# th-lora.net
KiCad netlist of a schematic drawn in EAGLE
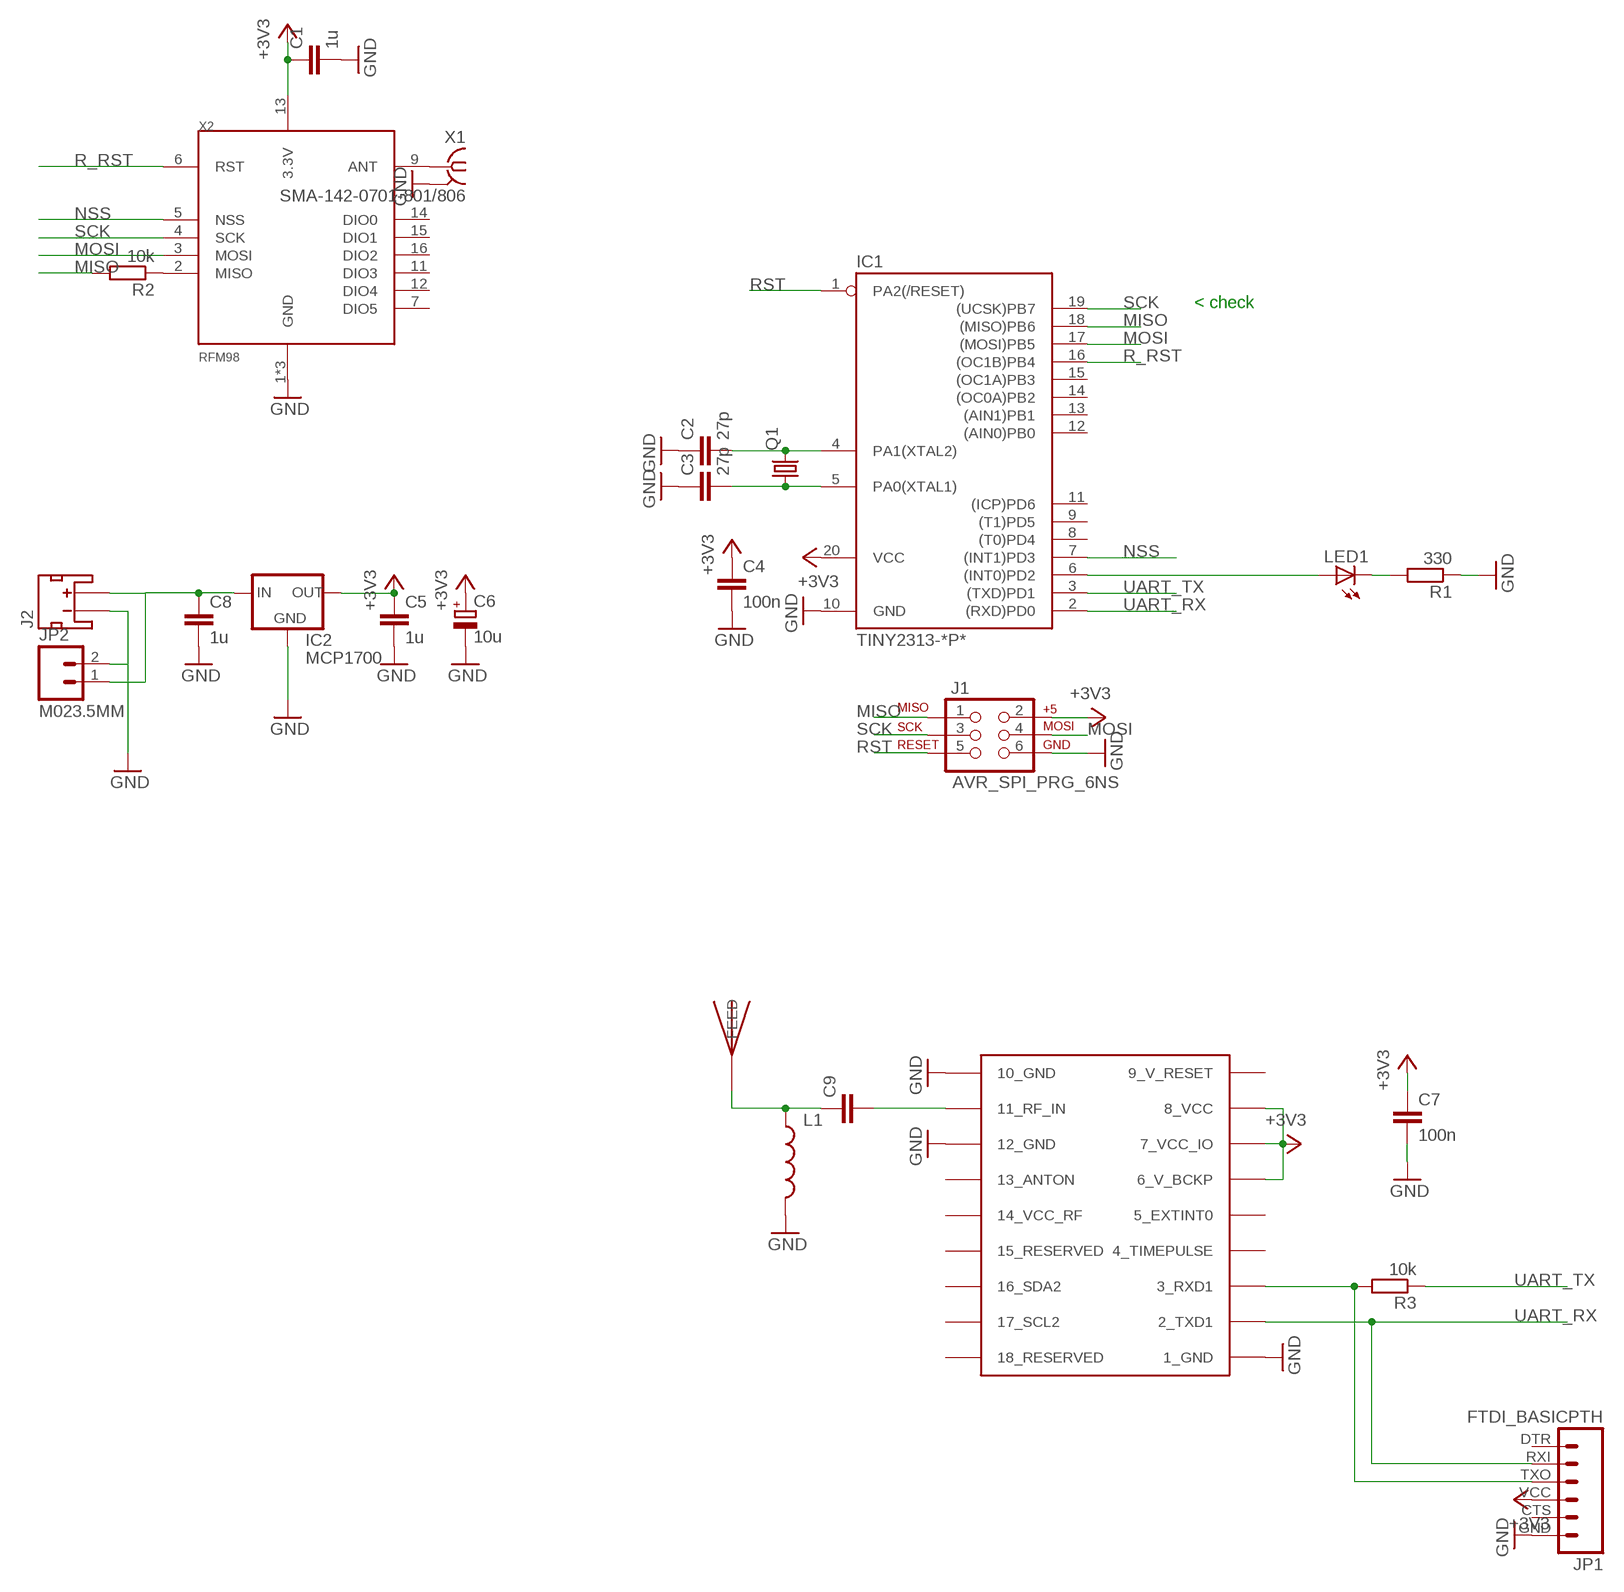
[diagram p0: schematic, sheet 1]

(export (version "E")
  (design (tool "Eeschema 10.0.6"))
  (components
    (comp (ref "C1")
      (value "1u")
      (footprint "eagle-import:C050-025X075")
      (libsource (lib "eagle-import") (part "C-EU050-025X075"))
    )
    (comp (ref "C2")
      (value "27p")
      (footprint "eagle-import:C050-025X075")
      (libsource (lib "eagle-import") (part "C-EU050-025X075"))
    )
    (comp (ref "C3")
      (value "27p")
      (footprint "eagle-import:C050-025X075")
      (libsource (lib "eagle-import") (part "C-EU050-025X075"))
    )
    (comp (ref "C4")
      (value "100n")
      (footprint "eagle-import:C050-025X075")
      (libsource (lib "eagle-import") (part "C-EU050-025X075"))
    )
    (comp (ref "C5")
      (value "1u")
      (footprint "eagle-import:C050-025X075")
      (libsource (lib "eagle-import") (part "C-EU050-025X075"))
    )
    (comp (ref "C6")
      (value "10u")
      (footprint "eagle-import:E2,5-5")
      (libsource (lib "eagle-import") (part "CPOL-EUE2.5-5"))
    )
    (comp (ref "C7")
      (value "100n")
      (footprint "eagle-import:C050-025X075")
      (libsource (lib "eagle-import") (part "C-EU050-025X075"))
    )
    (comp (ref "C8")
      (value "1u")
      (footprint "eagle-import:C050-025X075")
      (libsource (lib "eagle-import") (part "C-EU050-025X075"))
    )
    (comp (ref "C9")
      (value "C-EUC0603")
      (footprint "eagle-import:C0603")
      (libsource (lib "eagle-import") (part "C-EUC0603"))
    )
    (comp (ref "IC1")
      (value "TINY2313-*P*")
      (footprint "eagle-import:DIL20")
      (libsource (lib "eagle-import") (part "TINY2313-P"))
    )
    (comp (ref "IC2")
      (value "MCP1700")
      (footprint "eagle-import:TO92-INLINE")
      (libsource (lib "eagle-import") (part "MCP1700"))
    )
    (comp (ref "J1")
      (value "AVR_SPI_PRG_6NS")
      (footprint "eagle-import:2X3-NS")
      (libsource (lib "eagle-import") (part "AVR_SPI_PRG_6NS"))
    )
    (comp (ref "J2")
      (value "JST_2MM_MALE")
      (footprint "eagle-import:JST-2-SMD")
      (libsource (lib "eagle-import") (part "JST_2MM_MALE"))
    )
    (comp (ref "JP1")
      (value "FTDI_BASICPTH")
      (footprint "eagle-import:FTDI_BASIC")
      (libsource (lib "eagle-import") (part "FTDI_BASICPTH"))
    )
    (comp (ref "JP2")
      (value "M023.5MM")
      (footprint "eagle-import:SCREWTERMINAL-3.5MM-2")
      (libsource (lib "eagle-import") (part "M023.5MM"))
    )
    (comp (ref "L1")
      (value "INDUCTOR0603")
      (footprint "eagle-import:0603")
      (libsource (lib "eagle-import") (part "INDUCTOR0603"))
    )
    (comp (ref "LED1")
      (value "LED3MM")
      (footprint "eagle-import:LED3MM")
      (libsource (lib "eagle-import") (part "LED3MM"))
    )
    (comp (ref "Q1")
      (value "CRYSTALHC49S")
      (footprint "eagle-import:HC49_S")
      (libsource (lib "eagle-import") (part "CRYSTALHC49S"))
    )
    (comp (ref "R1")
      (value "330")
      (footprint "eagle-import:0204_7")
      (libsource (lib "eagle-import") (part "R-EU_0204/7"))
    )
    (comp (ref "R2")
      (value "10k")
      (footprint "eagle-import:0204_7")
      (libsource (lib "eagle-import") (part "R-EU_0204/7"))
    )
    (comp (ref "R3")
      (value "10k")
      (footprint "eagle-import:0204_7")
      (libsource (lib "eagle-import") (part "R-EU_0204/7"))
    )
    (comp (ref "U$3")
      (value "JTI_ANTENNA-1575AT43A40")
      (footprint "eagle-import:JTI_ANTENNA-1575AT43A40")
      (libsource (lib "eagle-import") (part "JTI_ANTENNA-1575AT43A40"))
    )
    (comp (ref "X1")
      (value "SMA-142-0701-801/806")
      (footprint "eagle-import:J502-ND-142-0701-801_806")
      (fields (field (name "MF") "JOHNSON COMPONENTS") (field (name "MPN") "142-0701-801"))
      (libsource (lib "eagle-import") (part "SMA-142-0701-801/806"))
    )
    (comp (ref "X2")
      (value "RFM98")
      (footprint "eagle-import:RFM97")
      (libsource (lib "eagle-import") (part "RFM98"))
    )
    (comp (ref "X3")
      (value "UBLOX_MAX")
      (footprint "eagle-import:UBLOX_MAX")
      (libsource (lib "eagle-import") (part "UBLOX_MAX"))
    )
  )
  (nets
    (net (code "1") (name "+3V3") (class "Default")
      (node (ref "C1") (pin "1") (pinfunction "1_1") (pintype "passive"))
      (node (ref "C4") (pin "1") (pinfunction "1_1") (pintype "passive"))
      (node (ref "C5") (pin "1") (pinfunction "1_1") (pintype "passive"))
      (node (ref "C6") (pin "+") (pinfunction "+_+") (pintype "passive"))
      (node (ref "C7") (pin "1") (pinfunction "1_1") (pintype "passive"))
      (node (ref "IC1") (pin "20") (pinfunction "VCC_20") (pintype "power_in"))
      (node (ref "IC2") (pin "VOUT") (pinfunction "OUT_VOUT") (pintype "passive"))
      (node (ref "J1") (pin "2") (pinfunction "2_2") (pintype "passive"))
      (node (ref "JP1") (pin "VCC") (pinfunction "4_VCC") (pintype "passive"))
      (node (ref "X2") (pin "13") (pinfunction "3.3V_13") (pintype "power_in"))
      (node (ref "X3") (pin "6_V_BCKP") (pinfunction "6_V_BCKP_6_V_BCKP") (pintype "bidirectional"))
      (node (ref "X3") (pin "7_VCC_IO") (pinfunction "7_VCC_IO_7_VCC_IO") (pintype "power_in"))
      (node (ref "X3") (pin "8_VCC") (pinfunction "8_VCC_8_VCC") (pintype "power_in"))
    )
    (net (code "2") (name "/9_V_RESET") (class "Default")
      (node (ref "X3") (pin "9_V_RESET") (pinfunction "9_V_RESET_9_V_RESET") (pintype "power_in"))
    )
    (net (code "3") (name "/MISO") (class "Default")
      (node (ref "IC1") (pin "18") (pinfunction "(MISO)PB6_18") (pintype "bidirectional"))
      (node (ref "J1") (pin "1") (pinfunction "1_1") (pintype "passive"))
      (node (ref "R2") (pin "2") (pinfunction "2_2") (pintype "passive"))
    )
    (net (code "4") (name "/MOSI") (class "Default")
      (node (ref "IC1") (pin "17") (pinfunction "(MOSI)PB5_17") (pintype "bidirectional"))
      (node (ref "J1") (pin "4") (pinfunction "4_4") (pintype "passive"))
      (node (ref "X2") (pin "3") (pinfunction "MOSI_3") (pintype "input"))
    )
    (net (code "5") (name "/NSS") (class "Default")
      (node (ref "IC1") (pin "7") (pinfunction "(INT1)PD3_7") (pintype "bidirectional"))
      (node (ref "X2") (pin "5") (pinfunction "NSS_5") (pintype "input"))
    )
    (net (code "6") (name "/RST") (class "Default")
      (node (ref "IC1") (pin "1") (pinfunction "PA2(/RESET)_1") (pintype "input"))
      (node (ref "J1") (pin "5") (pinfunction "5_5") (pintype "passive"))
    )
    (net (code "7") (name "/R_RST") (class "Default")
      (node (ref "IC1") (pin "16") (pinfunction "(OC1B)PB4_16") (pintype "bidirectional"))
      (node (ref "X2") (pin "6") (pinfunction "RST_6") (pintype "input"))
    )
    (net (code "8") (name "/SCK") (class "Default")
      (node (ref "IC1") (pin "19") (pinfunction "(UCSK)PB7_19") (pintype "bidirectional"))
      (node (ref "J1") (pin "3") (pinfunction "3_3") (pintype "passive"))
      (node (ref "X2") (pin "4") (pinfunction "SCK_4") (pintype "input"))
    )
    (net (code "9") (name "/UART_RX") (class "Default")
      (node (ref "IC1") (pin "2") (pinfunction "(RXD)PD0_2") (pintype "bidirectional"))
      (node (ref "JP1") (pin "RXI") (pinfunction "2_RXI") (pintype "passive"))
      (node (ref "X3") (pin "2_TXD1") (pinfunction "2_TXD1_2_TXD1") (pintype "bidirectional"))
    )
    (net (code "10") (name "/UART_TX") (class "Default")
      (node (ref "IC1") (pin "3") (pinfunction "(TXD)PD1_3") (pintype "bidirectional"))
      (node (ref "R3") (pin "1") (pinfunction "1_1") (pintype "passive"))
    )
    (net (code "11") (name "GND") (class "Default")
      (node (ref "C1") (pin "2") (pinfunction "2_2") (pintype "passive"))
      (node (ref "C2") (pin "1") (pinfunction "1_1") (pintype "passive"))
      (node (ref "C3") (pin "1") (pinfunction "1_1") (pintype "passive"))
      (node (ref "C4") (pin "2") (pinfunction "2_2") (pintype "passive"))
      (node (ref "C5") (pin "2") (pinfunction "2_2") (pintype "passive"))
      (node (ref "C6") (pin "-") (pinfunction "-_-") (pintype "passive"))
      (node (ref "C7") (pin "2") (pinfunction "2_2") (pintype "passive"))
      (node (ref "C8") (pin "2") (pinfunction "2_2") (pintype "passive"))
      (node (ref "IC1") (pin "10") (pinfunction "GND_10") (pintype "power_in"))
      (node (ref "IC2") (pin "GND") (pinfunction "GND_GND") (pintype "input"))
      (node (ref "J1") (pin "6") (pinfunction "6_6") (pintype "passive"))
      (node (ref "J2") (pin "1") (pinfunction "-_1") (pintype "bidirectional"))
      (node (ref "JP1") (pin "GND") (pinfunction "6_GND") (pintype "passive"))
      (node (ref "JP2") (pin "2") (pinfunction "2_2") (pintype "passive"))
      (node (ref "L1") (pin "2") (pinfunction "2_2") (pintype "passive"))
      (node (ref "R1") (pin "1") (pinfunction "1_1") (pintype "passive"))
      (node (ref "X1") (pin "G@1") (pinfunction "2_G@1") (pintype "passive"))
      (node (ref "X1") (pin "G@2") (pinfunction "2_G@2") (pintype "passive"))
      (node (ref "X1") (pin "G@3") (pinfunction "2_G@3") (pintype "passive"))
      (node (ref "X1") (pin "G@4") (pinfunction "2_G@4") (pintype "passive"))
      (node (ref "X2") (pin "1") (pinfunction "GND_1") (pintype "power_in"))
      (node (ref "X2") (pin "10") (pinfunction "GND_10") (pintype "power_in"))
      (node (ref "X2") (pin "8") (pinfunction "GND_8") (pintype "power_in"))
      (node (ref "X3") (pin "10_GND") (pinfunction "10_GND_10_GND") (pintype "power_in"))
      (node (ref "X3") (pin "12_GND") (pinfunction "12_GND_12_GND") (pintype "power_in"))
      (node (ref "X3") (pin "1_GND") (pinfunction "1_GND_1_GND") (pintype "power_in"))
    )
    (net (code "12") (name "Net-(C9-Pad1)") (class "Default")
      (node (ref "C9") (pin "1") (pinfunction "1_1") (pintype "passive"))
      (node (ref "L1") (pin "1") (pinfunction "1_1") (pintype "passive"))
      (node (ref "U$3") (pin "FEED") (pinfunction "FEED_FEED") (pintype "bidirectional"))
    )
    (net (code "13") (name "Net-(C9-Pad2)") (class "Default")
      (node (ref "C9") (pin "2") (pinfunction "2_2") (pintype "passive"))
      (node (ref "X3") (pin "11_RF_IN") (pinfunction "11_RF_IN_11_RF_IN") (pintype "bidirectional"))
    )
    (net (code "14") (name "Net-(IC1-(INT0)PD2)") (class "Default")
      (node (ref "IC1") (pin "6") (pinfunction "(INT0)PD2_6") (pintype "bidirectional"))
      (node (ref "LED1") (pin "A") (pinfunction "A_A") (pintype "passive"))
    )
    (net (code "15") (name "Net-(IC1-PA0(XTAL1))") (class "Default")
      (node (ref "C3") (pin "2") (pinfunction "2_2") (pintype "passive"))
      (node (ref "IC1") (pin "5") (pinfunction "PA0(XTAL1)_5") (pintype "bidirectional"))
      (node (ref "Q1") (pin "1") (pinfunction "1_1") (pintype "passive"))
    )
    (net (code "16") (name "Net-(IC1-PA1(XTAL2))") (class "Default")
      (node (ref "C2") (pin "2") (pinfunction "2_2") (pintype "passive"))
      (node (ref "IC1") (pin "4") (pinfunction "PA1(XTAL2)_4") (pintype "bidirectional"))
      (node (ref "Q1") (pin "2") (pinfunction "2_2") (pintype "passive"))
    )
    (net (code "17") (name "Net-(IC2-IN)") (class "Default")
      (node (ref "C8") (pin "1") (pinfunction "1_1") (pintype "passive"))
      (node (ref "IC2") (pin "VIN") (pinfunction "IN_VIN") (pintype "input"))
      (node (ref "J2") (pin "2") (pinfunction "+_2") (pintype "bidirectional"))
      (node (ref "JP2") (pin "1") (pinfunction "1_1") (pintype "passive"))
    )
    (net (code "18") (name "Net-(JP1-3)") (class "Default")
      (node (ref "JP1") (pin "TXO") (pinfunction "3_TXO") (pintype "passive"))
      (node (ref "R3") (pin "2") (pinfunction "2_2") (pintype "passive"))
      (node (ref "X3") (pin "3_RXD1") (pinfunction "3_RXD1_3_RXD1") (pintype "bidirectional"))
    )
    (net (code "19") (name "Net-(LED1-C)") (class "Default")
      (node (ref "LED1") (pin "K") (pinfunction "C_K") (pintype "passive"))
      (node (ref "R1") (pin "2") (pinfunction "2_2") (pintype "passive"))
    )
    (net (code "20") (name "Net-(X2-ANT)") (class "Default")
      (node (ref "X1") (pin "1") (pinfunction "1_1") (pintype "passive"))
      (node (ref "X2") (pin "9") (pinfunction "ANT_9") (pintype "bidirectional"))
    )
    (net (code "21") (name "Net-(X2-MISO)") (class "Default")
      (node (ref "R2") (pin "1") (pinfunction "1_1") (pintype "passive"))
      (node (ref "X2") (pin "2") (pinfunction "MISO_2") (pintype "output"))
    )
    (net (code "22") (name "unconnected-(IC1-(AIN0)PB0-Pad12)") (class "Default")
      (node (ref "IC1") (pin "12") (pinfunction "(AIN0)PB0_12") (pintype "bidirectional"))
    )
    (net (code "23") (name "unconnected-(IC1-(AIN1)PB1-Pad13)") (class "Default")
      (node (ref "IC1") (pin "13") (pinfunction "(AIN1)PB1_13") (pintype "bidirectional"))
    )
    (net (code "24") (name "unconnected-(IC1-(ICP)PD6-Pad11)") (class "Default")
      (node (ref "IC1") (pin "11") (pinfunction "(ICP)PD6_11") (pintype "bidirectional"))
    )
    (net (code "25") (name "unconnected-(IC1-(OC0A)PB2-Pad14)") (class "Default")
      (node (ref "IC1") (pin "14") (pinfunction "(OC0A)PB2_14") (pintype "bidirectional"))
    )
    (net (code "26") (name "unconnected-(IC1-(OC1A)PB3-Pad15)") (class "Default")
      (node (ref "IC1") (pin "15") (pinfunction "(OC1A)PB3_15") (pintype "bidirectional"))
    )
    (net (code "27") (name "unconnected-(IC1-(T0)PD4-Pad8)") (class "Default")
      (node (ref "IC1") (pin "8") (pinfunction "(T0)PD4_8") (pintype "bidirectional"))
    )
    (net (code "28") (name "unconnected-(IC1-(T1)PD5-Pad9)") (class "Default")
      (node (ref "IC1") (pin "9") (pinfunction "(T1)PD5_9") (pintype "bidirectional"))
    )
    (net (code "29") (name "unconnected-(J2-PAD1-PadNC1)") (class "Default")
      (node (ref "J2") (pin "NC1") (pinfunction "PAD1_NC1") (pintype "bidirectional"))
    )
    (net (code "30") (name "unconnected-(J2-PAD2-PadNC2)") (class "Default")
      (node (ref "J2") (pin "NC2") (pinfunction "PAD2_NC2") (pintype "bidirectional"))
    )
    (net (code "31") (name "unconnected-(JP1-1-PadDTR)") (class "Default")
      (node (ref "JP1") (pin "DTR") (pinfunction "1_DTR") (pintype "passive"))
    )
    (net (code "32") (name "unconnected-(JP1-5-PadCTS)") (class "Default")
      (node (ref "JP1") (pin "CTS") (pinfunction "5_CTS") (pintype "passive"))
    )
    (net (code "33") (name "unconnected-(X2-DIO0-Pad14)") (class "Default")
      (node (ref "X2") (pin "14") (pinfunction "DIO0_14") (pintype "bidirectional"))
    )
    (net (code "34") (name "unconnected-(X2-DIO1-Pad15)") (class "Default")
      (node (ref "X2") (pin "15") (pinfunction "DIO1_15") (pintype "bidirectional"))
    )
    (net (code "35") (name "unconnected-(X2-DIO2-Pad16)") (class "Default")
      (node (ref "X2") (pin "16") (pinfunction "DIO2_16") (pintype "bidirectional"))
    )
    (net (code "36") (name "unconnected-(X2-DIO3-Pad11)") (class "Default")
      (node (ref "X2") (pin "11") (pinfunction "DIO3_11") (pintype "bidirectional"))
    )
    (net (code "37") (name "unconnected-(X2-DIO4-Pad12)") (class "Default")
      (node (ref "X2") (pin "12") (pinfunction "DIO4_12") (pintype "bidirectional"))
    )
    (net (code "38") (name "unconnected-(X2-DIO5-Pad7)") (class "Default")
      (node (ref "X2") (pin "7") (pinfunction "DIO5_7") (pintype "bidirectional"))
    )
    (net (code "39") (name "unconnected-(X3-Pad4_TIMEPULSE)") (class "Default")
      (node (ref "X3") (pin "4_TIMEPULSE") (pinfunction "4_TIMEPULSE_4_TIMEPULSE") (pintype "bidirectional"))
    )
    (net (code "40") (name "unconnected-(X3-Pad5_EXTINT0)") (class "Default")
      (node (ref "X3") (pin "5_EXTINT0") (pinfunction "5_EXTINT0_5_EXTINT0") (pintype "bidirectional"))
    )
    (net (code "41") (name "unconnected-(X3-Pad13_ANTON)") (class "Default")
      (node (ref "X3") (pin "13_ANTON") (pinfunction "13_ANTON_13_ANTON") (pintype "bidirectional"))
    )
    (net (code "42") (name "unconnected-(X3-Pad14_VCC_RF)") (class "Default")
      (node (ref "X3") (pin "14_VCC_RF") (pinfunction "14_VCC_RF_14_VCC_RF") (pintype "bidirectional"))
    )
    (net (code "43") (name "unconnected-(X3-Pad15_RESERVED)") (class "Default")
      (node (ref "X3") (pin "15_RESERVED") (pinfunction "15_RESERVED_15_RESERVED") (pintype "bidirectional"))
    )
    (net (code "44") (name "unconnected-(X3-Pad16_SDA2)") (class "Default")
      (node (ref "X3") (pin "16_SDA2") (pinfunction "16_SDA2_16_SDA2") (pintype "bidirectional"))
    )
    (net (code "45") (name "unconnected-(X3-Pad17_SCL2)") (class "Default")
      (node (ref "X3") (pin "17_SCL2") (pinfunction "17_SCL2_17_SCL2") (pintype "bidirectional"))
    )
    (net (code "46") (name "unconnected-(X3-Pad18_RESERVED)") (class "Default")
      (node (ref "X3") (pin "18_RESERVED") (pinfunction "18_RESERVED_18_RESERVED") (pintype "bidirectional"))
    )
  )
)
